# LB_BIT_iX_1IN_1OUT-LARGE_v03_1_1x.net
KiCad netlist of a schematic drawn in EAGLE
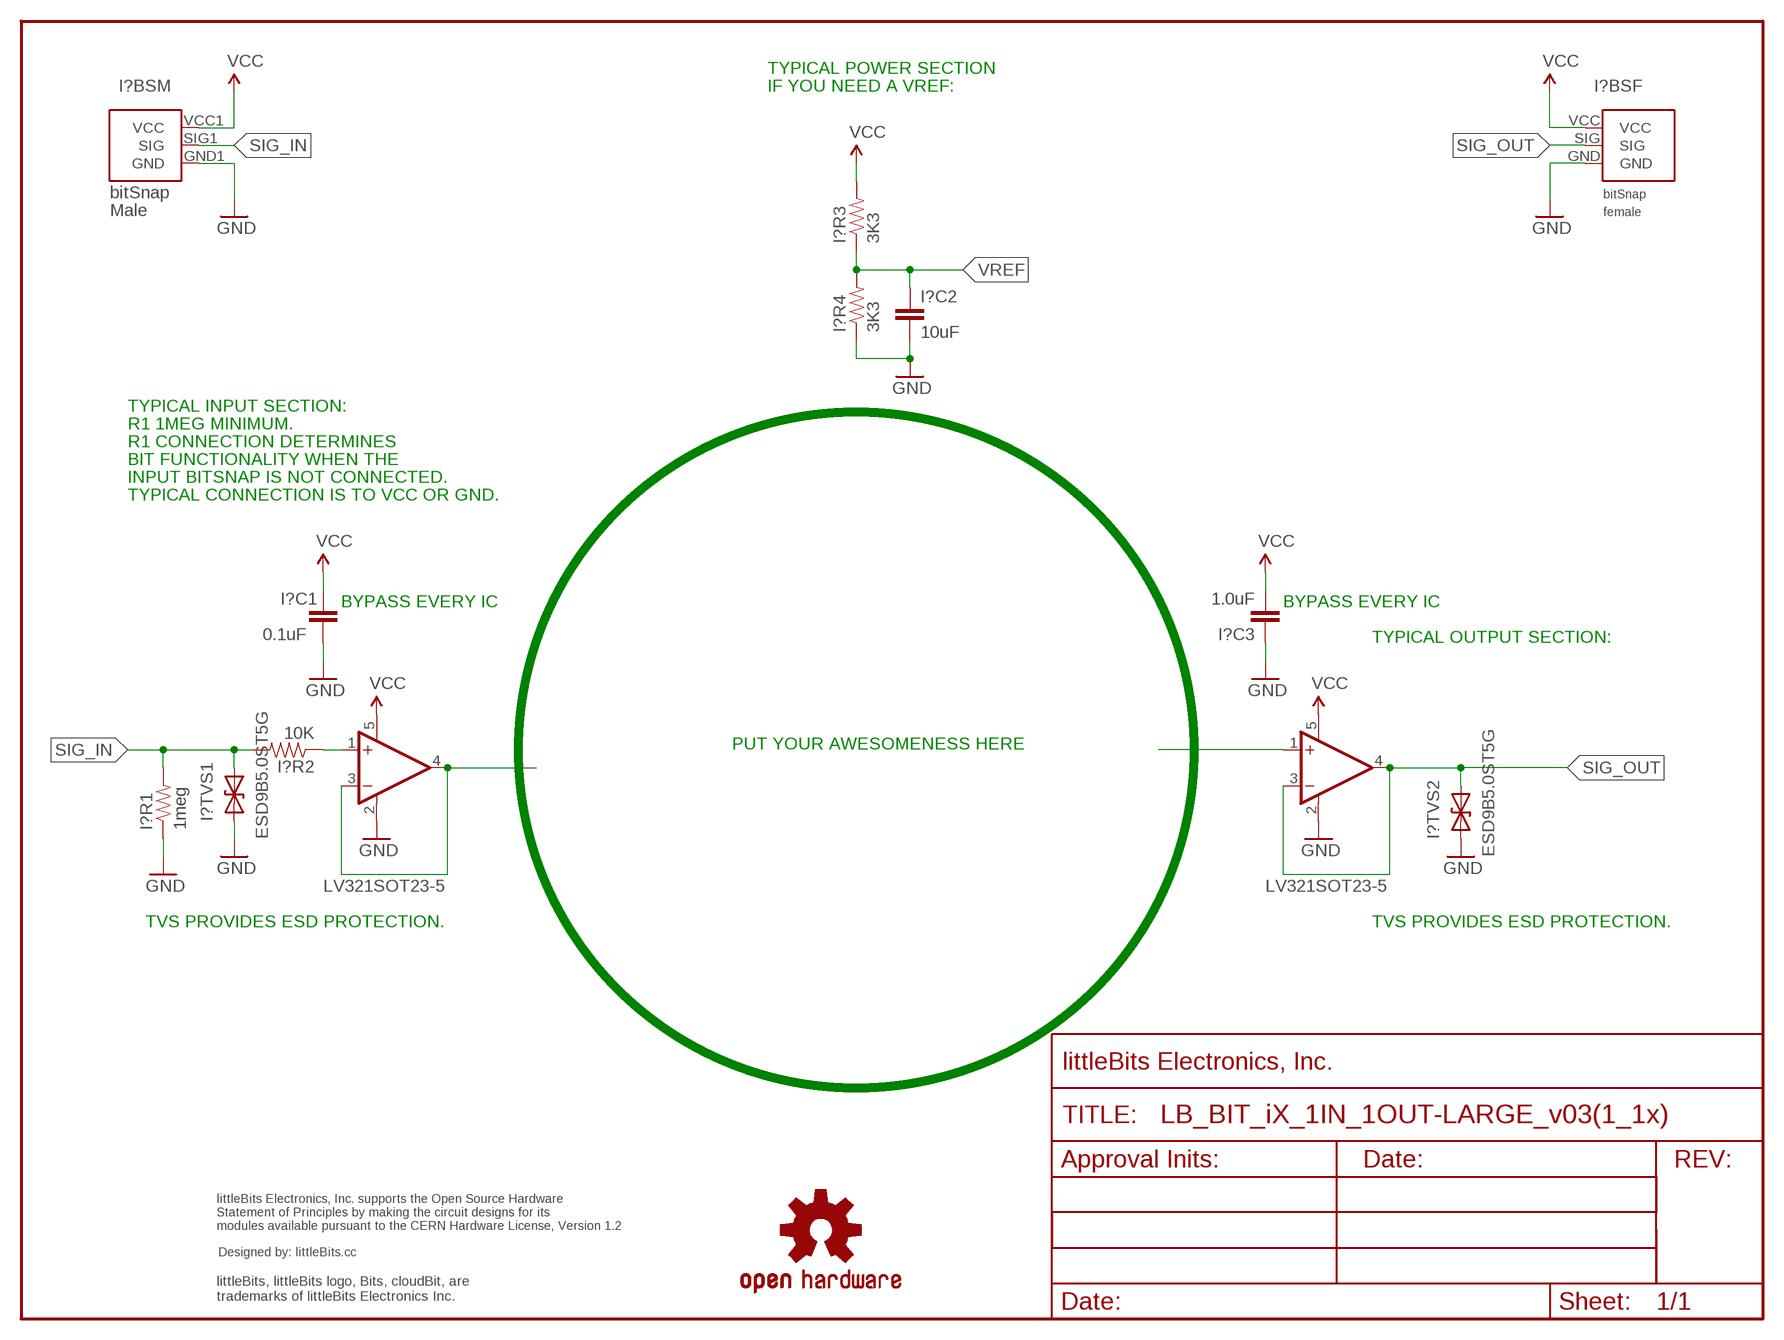
[diagram p0: schematic, sheet 1]

(export (version "E")
  (design (tool "Eeschema 10.0.6"))
  (components
    (comp (ref "FRAME1")
      (value "FRAME-LETTER")
      (footprint "eagle-import:FABDWG01-OHW")
      (libsource (lib "eagle-import") (part "FRAME-LETTER"))
    )
    (comp (ref "I?BSF")
      (value "BITSNAP_V03_FEMALE")
      (footprint "eagle-import:BITSNAP_V03_FEMALE")
      (libsource (lib "eagle-import") (part "BITSNAP_V03_FEMALE"))
    )
    (comp (ref "I?BSM")
      (value "BITSNAP_V03_MALE")
      (footprint "eagle-import:BITSNAP_V03_MALE")
      (libsource (lib "eagle-import") (part "BITSNAP_V03_MALE"))
    )
    (comp (ref "I?C1")
      (value "0.1uF")
      (footprint "eagle-import:CAP-0603")
      (libsource (lib "eagle-import") (part "CAPCAP-0603"))
    )
    (comp (ref "I?C2")
      (value "10uF")
      (footprint "eagle-import:CAP-0603")
      (libsource (lib "eagle-import") (part "CAPCAP-0603"))
    )
    (comp (ref "I?C3")
      (value "1.0uF")
      (footprint "eagle-import:CAP-0603")
      (libsource (lib "eagle-import") (part "CAPCAP-0603"))
    )
    (comp (ref "I?R1")
      (value "1meg")
      (footprint "eagle-import:RES-0603")
      (libsource (lib "eagle-import") (part "RESISTOR0603"))
    )
    (comp (ref "I?R2")
      (value "10K")
      (footprint "eagle-import:RES-0603")
      (libsource (lib "eagle-import") (part "RESISTOR0603"))
    )
    (comp (ref "I?R3")
      (value "3K3")
      (footprint "eagle-import:RES-0603")
      (libsource (lib "eagle-import") (part "RESISTOR0603"))
    )
    (comp (ref "I?R4")
      (value "3K3")
      (footprint "eagle-import:RES-0603")
      (libsource (lib "eagle-import") (part "RESISTOR0603"))
    )
    (comp (ref "I?TVS1")
      (value "ESD9B5.0ST5G")
      (footprint "eagle-import:SOD-923")
      (libsource (lib "eagle-import") (part "DIODE-TVSSOD-923"))
    )
    (comp (ref "I?TVS2")
      (value "ESD9B5.0ST5G")
      (footprint "eagle-import:SOD-923")
      (libsource (lib "eagle-import") (part "DIODE-TVSSOD-923"))
    )
    (comp (ref "U$1")
      (value "OSHWCREDIT")
      (footprint "eagle-import:OSHWCREDIT")
      (libsource (lib "eagle-import") (part "OSHWCREDIT"))
    )
    (comp (ref "U$4")
      (value "OSHW-LOGOL")
      (footprint "eagle-import:OSHW-LOGO-L")
      (libsource (lib "eagle-import") (part "OSHW-LOGOL"))
    )
    (comp (ref "U1")
      (value "LV321SOT23-5")
      (footprint "eagle-import:SOT23-5")
      (libsource (lib "eagle-import") (part "LV321SOT23-5"))
    )
    (comp (ref "U2")
      (value "LV321SOT23-5")
      (footprint "eagle-import:SOT23-5")
      (libsource (lib "eagle-import") (part "LV321SOT23-5"))
    )
  )
  (nets
    (net (code "1") (name "GND") (class "Default")
      (node (ref "I?BSF") (pin "GND") (pinfunction "GND_GND") (pintype "bidirectional"))
      (node (ref "I?BSM") (pin "GND1") (pinfunction "GND_GND1") (pintype "bidirectional"))
      (node (ref "I?C1") (pin "2") (pinfunction "2_2") (pintype "passive"))
      (node (ref "I?C2") (pin "2") (pinfunction "2_2") (pintype "passive"))
      (node (ref "I?C3") (pin "1") (pinfunction "1_1") (pintype "passive"))
      (node (ref "I?R1") (pin "1") (pinfunction "1_1") (pintype "passive"))
      (node (ref "I?R4") (pin "1") (pinfunction "1_1") (pintype "passive"))
      (node (ref "I?TVS1") (pin "1") (pinfunction "A_1") (pintype "passive"))
      (node (ref "I?TVS2") (pin "1") (pinfunction "A_1") (pintype "passive"))
      (node (ref "U1") (pin "2") (pinfunction "V-_2") (pintype "power_in"))
      (node (ref "U2") (pin "2") (pinfunction "V-_2") (pintype "power_in"))
    )
    (net (code "2") (name "Net-(U1-+IN)") (class "Default")
      (node (ref "I?R2") (pin "1") (pinfunction "1_1") (pintype "passive"))
      (node (ref "U1") (pin "1") (pinfunction "+IN_1") (pintype "input"))
    )
    (net (code "3") (name "Net-(U1--IN)") (class "Default")
      (node (ref "U1") (pin "3") (pinfunction "-IN_3") (pintype "input"))
      (node (ref "U1") (pin "4") (pinfunction "OUT_4") (pintype "output"))
    )
    (net (code "4") (name "SIG_IN") (class "Default")
      (node (ref "I?BSM") (pin "SIG1") (pinfunction "SIG_SIG1") (pintype "bidirectional"))
      (node (ref "I?R1") (pin "2") (pinfunction "2_2") (pintype "passive"))
      (node (ref "I?R2") (pin "2") (pinfunction "2_2") (pintype "passive"))
      (node (ref "I?TVS1") (pin "2") (pinfunction "C_2") (pintype "passive"))
    )
    (net (code "5") (name "SIG_OUT") (class "Default")
      (node (ref "I?BSF") (pin "SIG") (pinfunction "SIG_SIG") (pintype "bidirectional"))
      (node (ref "I?TVS2") (pin "2") (pinfunction "C_2") (pintype "passive"))
      (node (ref "U2") (pin "3") (pinfunction "-IN_3") (pintype "input"))
      (node (ref "U2") (pin "4") (pinfunction "OUT_4") (pintype "output"))
    )
    (net (code "6") (name "VCC") (class "Default")
      (node (ref "I?BSF") (pin "VCC") (pinfunction "VCC_VCC") (pintype "bidirectional"))
      (node (ref "I?BSM") (pin "VCC1") (pinfunction "VCC_VCC1") (pintype "bidirectional"))
      (node (ref "I?C1") (pin "1") (pinfunction "1_1") (pintype "passive"))
      (node (ref "I?C3") (pin "2") (pinfunction "2_2") (pintype "passive"))
      (node (ref "I?R3") (pin "2") (pinfunction "2_2") (pintype "passive"))
      (node (ref "U1") (pin "5") (pinfunction "V+_5") (pintype "power_in"))
      (node (ref "U2") (pin "5") (pinfunction "V+_5") (pintype "power_in"))
    )
    (net (code "7") (name "VREF") (class "Default")
      (node (ref "I?C2") (pin "1") (pinfunction "1_1") (pintype "passive"))
      (node (ref "I?R3") (pin "1") (pinfunction "1_1") (pintype "passive"))
      (node (ref "I?R4") (pin "2") (pinfunction "2_2") (pintype "passive"))
    )
    (net (code "8") (name "unconnected-(U2-+IN-Pad1)") (class "Default")
      (node (ref "U2") (pin "1") (pinfunction "+IN_1") (pintype "input"))
    )
  )
)
